# LTM8074neg.net
KiCad netlist of a schematic drawn in Altium Designer
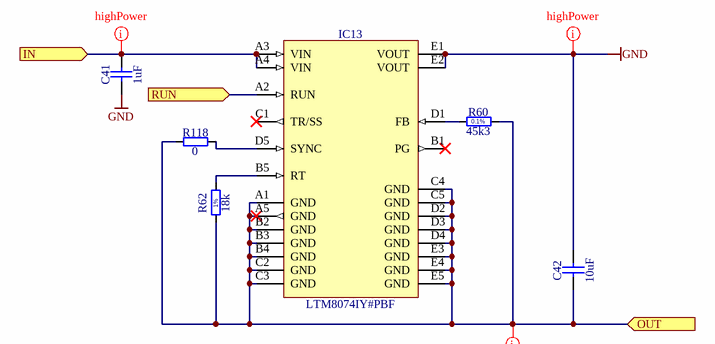
[diagram p0: LTM8074neg.SchDoc]

(export (version "E")
  (design (tool "Eeschema 10.0.6"))
  (components
    (comp (ref "C41")
      (value "1uF")
      (footprint "CAPC2012X110N")
      (description "Non-polarised capacitor")
      (fields
        (field (name "PART NUMBER") "CC0805_1UF_50V_10%_X7R")
        (field (name "VOLTAGE") "50V")
        (field (name "AUTHOR") "CERN DEM JLC")
      )
      (libsource (lib "Capacitors") (part "Capacitor - non polarized"))
    )
    (comp (ref "C42")
      (value "10uF")
      (footprint "CAPC2012X95N")
      (description "Non-polarised capacitor")
      (fields
        (field (name "PART NUMBER") "CC0805_10UF_25V_10%_X5R")
        (field (name "VOLTAGE") "25V")
        (field (name "AUTHOR") "CERN DEM JLC")
      )
      (libsource (lib "Capacitors") (part "Capacitor - non polarized"))
    )
    (comp (ref "IC13")
      (value "LTM8074IY#PBF")
      (footprint "BGA25C65P5X5_400X400X198")
      (description "40VIN, 1.2A Silent Switcher µModule Regulator")
      (fields (field (name "MANUFACTURER") "LINEAR TECHNOLOGY") (field (name "AUTHOR") "CERN DEM JLC"))
      (libsource (lib "ICs And Semiconductors") (part "LTM8074"))
    )
    (comp (ref "R60")
      (value "45k3")
      (footprint "RESC1608X55N")
      (description "Resistor - 0.1%")
      (fields
        (field (name "PART NUMBER") "R0603_45K3_0.1%_0.063W_10PPM")
        (field (name "POWER") "0.063W")
        (field (name "AUTHOR") "CERN DEM JLC")
      )
      (libsource (lib "Resistors") (part "Resistor - 0.1%"))
    )
    (comp (ref "R62")
      (value "18k")
      (footprint "RESC1608X55N")
      (description "Resistor - 1%")
      (fields
        (field (name "PART NUMBER") "R0603_18K_1%_0.1W_100PPM")
        (field (name "POWER") "0.1W")
        (field (name "AUTHOR") "CERN DEM JLC")
      )
      (libsource (lib "Resistors") (part "Resistor - 1%"))
    )
    (comp (ref "R118")
      (value "0")
      (footprint "RESC1608X55N")
      (description "Resistor")
      (fields
        (field (name "PART NUMBER") "R0603_0R_JUMPER")
        (field (name "MANUFACTURER") "GENERIC")
        (field (name "AUTHOR") "CERN DEM JLC")
      )
      (libsource (lib "Resistors") (part "Resistor"))
    )
  )
  (nets
    (net (code "1") (name "/IN") (class "Default")
      (node (ref "C41") (pin "2") (pinfunction "2_2") (pintype "passive"))
      (node (ref "IC13") (pin "A3") (pinfunction "VIN_A3") (pintype "input"))
      (node (ref "IC13") (pin "A4") (pinfunction "VIN_A4") (pintype "input"))
    )
    (net (code "2") (name "/OUT") (class "Default")
      (node (ref "C42") (pin "1") (pinfunction "1_1") (pintype "passive"))
      (node (ref "IC13") (pin "A1") (pinfunction "GND_A1") (pintype "power_in"))
      (node (ref "IC13") (pin "A5") (pinfunction "GND_A5") (pintype "output"))
      (node (ref "IC13") (pin "B2") (pinfunction "GND_B2") (pintype "power_in"))
      (node (ref "IC13") (pin "B3") (pinfunction "GND_B3") (pintype "power_in"))
      (node (ref "IC13") (pin "B4") (pinfunction "GND_B4") (pintype "power_in"))
      (node (ref "IC13") (pin "C2") (pinfunction "GND_C2") (pintype "power_in"))
      (node (ref "IC13") (pin "C3") (pinfunction "GND_C3") (pintype "power_in"))
      (node (ref "IC13") (pin "C4") (pinfunction "GND_C4") (pintype "power_in"))
      (node (ref "IC13") (pin "C5") (pinfunction "GND_C5") (pintype "power_in"))
      (node (ref "IC13") (pin "D2") (pinfunction "GND_D2") (pintype "power_in"))
      (node (ref "IC13") (pin "D3") (pinfunction "GND_D3") (pintype "power_in"))
      (node (ref "IC13") (pin "D4") (pinfunction "GND_D4") (pintype "power_in"))
      (node (ref "IC13") (pin "E3") (pinfunction "GND_E3") (pintype "power_in"))
      (node (ref "IC13") (pin "E4") (pinfunction "GND_E4") (pintype "power_in"))
      (node (ref "IC13") (pin "E5") (pinfunction "GND_E5") (pintype "power_in"))
      (node (ref "R118") (pin "1") (pinfunction "1_1") (pintype "passive"))
      (node (ref "R60") (pin "2") (pinfunction "2_2") (pintype "passive"))
      (node (ref "R62") (pin "1") (pinfunction "1_1") (pintype "passive"))
    )
    (net (code "3") (name "/RUN") (class "Default")
      (node (ref "IC13") (pin "A2") (pinfunction "RUN_A2") (pintype "input"))
    )
    (net (code "4") (name "GND") (class "Default")
      (node (ref "C41") (pin "1") (pinfunction "1_1") (pintype "passive"))
      (node (ref "C42") (pin "2") (pinfunction "2_2") (pintype "passive"))
      (node (ref "IC13") (pin "E1") (pinfunction "VOUT_E1") (pintype "power_in"))
      (node (ref "IC13") (pin "E2") (pinfunction "VOUT_E2") (pintype "power_in"))
    )
    (net (code "5") (name "Net-(IC13-FB)") (class "Default")
      (node (ref "IC13") (pin "D1") (pinfunction "FB_D1") (pintype "input"))
      (node (ref "R60") (pin "1") (pinfunction "1_1") (pintype "passive"))
    )
    (net (code "6") (name "Net-(IC13-RT)") (class "Default")
      (node (ref "IC13") (pin "B5") (pinfunction "RT_B5") (pintype "input"))
      (node (ref "R62") (pin "2") (pinfunction "2_2") (pintype "passive"))
    )
    (net (code "7") (name "Net-(IC13-SYNC)") (class "Default")
      (node (ref "IC13") (pin "D5") (pinfunction "SYNC_D5") (pintype "input"))
      (node (ref "R118") (pin "2") (pinfunction "2_2") (pintype "passive"))
    )
    (net (code "8") (name "unconnected-(IC13-PG-PadB1)") (class "Default")
      (node (ref "IC13") (pin "B1") (pinfunction "PG_B1") (pintype "output+no_connect"))
    )
    (net (code "9") (name "unconnected-(IC13-TR{slash}SS-PadC1)") (class "Default")
      (node (ref "IC13") (pin "C1") (pinfunction "TR/SS_C1") (pintype "output+no_connect"))
    )
  )
)
